# mbed_programmer_2.net
KiCad netlist of a schematic drawn in Altium Designer
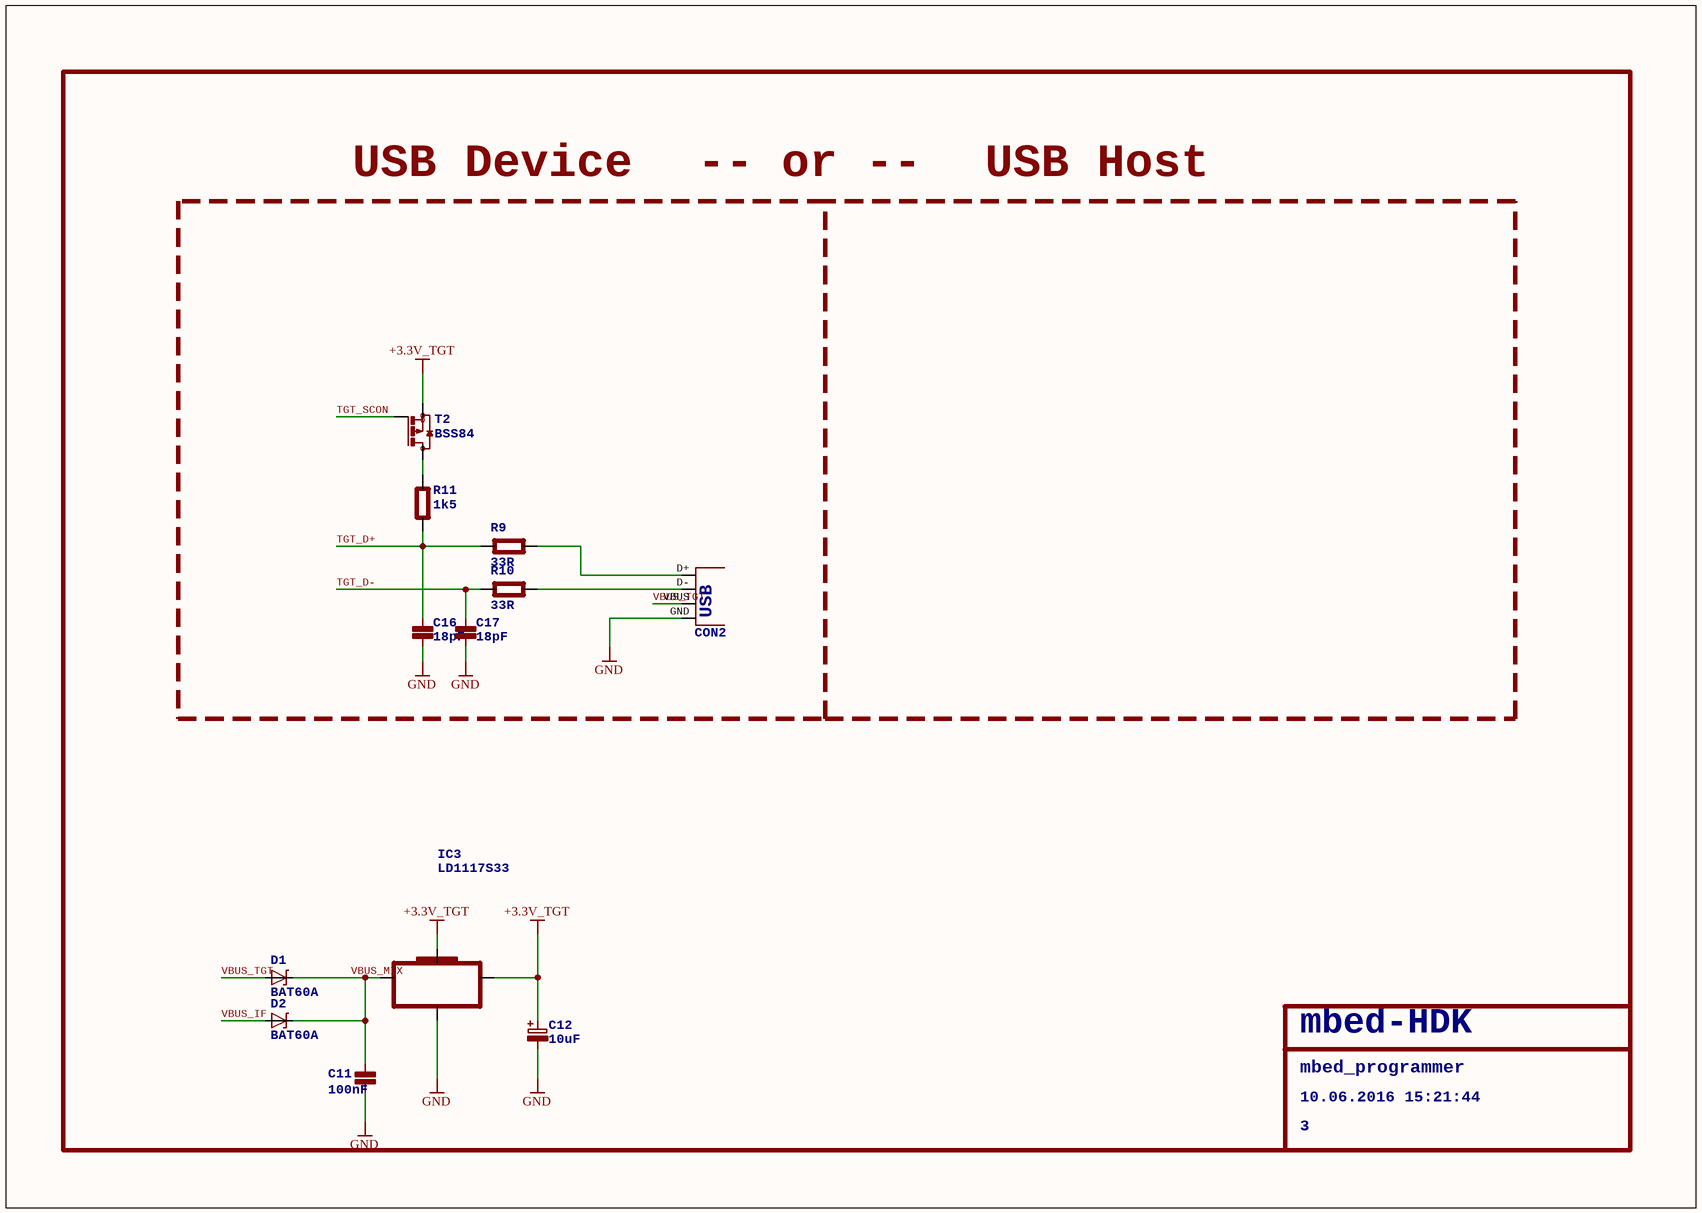
[diagram p0: mbed_programmer_2.SchDoc]

(export (version "E")
  (design (tool "Eeschema 10.0.6"))
  (components
    (comp (ref "C11") (value "100nF") (footprint "0603") (libsource (lib "mbed-HDK") (part "C0603")))
    (comp (ref "C12") (value "10uF") (footprint "CASE-B") (libsource (lib "mbed-HDK") (part "C-POLB")))
    (comp (ref "C16") (value "18pF") (footprint "0603") (libsource (lib "mbed-HDK") (part "C0603")))
    (comp (ref "C17") (value "18pF") (footprint "0603") (libsource (lib "mbed-HDK") (part "C0603")))
    (comp (ref "CON2")
      (value "USB-MB-S")
      (footprint "USB-MB-S")
      (description "USB Connectors")
      (fields (field (name "USB") "USB"))
      (libsource (lib "mbed-HDK") (part "USB-MB-S"))
    )
    (comp (ref "D1") (value "BAT60A") (footprint "BAT60A") (libsource (lib "mbed-HDK") (part "BAT60A")))
    (comp (ref "D2") (value "BAT60A") (footprint "BAT60A") (libsource (lib "mbed-HDK") (part "BAT60A")))
    (comp (ref "IC3")
      (value "LD1117S33")
      (footprint "SOT223")
      (description "VOLTAGE REGULATOR SMD 3,3V")
      (libsource (lib "mbed-HDK") (part "LD1117S33"))
    )
    (comp (ref "R9") (value "33R") (footprint "0603") (libsource (lib "mbed-HDK") (part "R0603")))
    (comp (ref "R10") (value "33R") (footprint "0603") (libsource (lib "mbed-HDK") (part "R0603")))
    (comp (ref "R11") (value "1k5") (footprint "0603") (libsource (lib "mbed-HDK") (part "R0603")))
    (comp (ref "T2")
      (value "BSS84")
      (footprint "SOT23")
      (description "P-CHANNEL MOS FET")
      (libsource (lib "mbed-HDK") (part "BSS84"))
    )
  )
  (nets
    (net (code "1") (name "+3.3V_TGT") (class "Default")
      (node (ref "C12") (pin "1") (pinfunction "1_1") (pintype "passive"))
      (node (ref "IC3") (pin "2") (pinfunction "OUT_2") (pintype "passive"))
      (node (ref "IC3") (pin "4") (pinfunction "K_4") (pintype "passive"))
      (node (ref "T2") (pin "2") (pinfunction "S_2") (pintype "passive"))
    )
    (net (code "2") (name "/TGT_D+") (class "Default")
      (node (ref "C16") (pin "1") (pinfunction "P$1_1") (pintype "passive"))
      (node (ref "R11") (pin "2") (pinfunction "P$2_2") (pintype "passive"))
      (node (ref "R9") (pin "1") (pinfunction "P$1_1") (pintype "passive"))
    )
    (net (code "3") (name "/TGT_D-") (class "Default")
      (node (ref "C17") (pin "1") (pinfunction "P$1_1") (pintype "passive"))
      (node (ref "R10") (pin "1") (pinfunction "P$1_1") (pintype "passive"))
    )
    (net (code "4") (name "/TGT_SCON") (class "Default")
      (node (ref "T2") (pin "1") (pinfunction "G_1") (pintype "passive"))
    )
    (net (code "5") (name "/VBUS_IF") (class "Default")
      (node (ref "D2") (pin "A") (pinfunction "A_A") (pintype "passive"))
    )
    (net (code "6") (name "/VBUS_MIX") (class "Default")
      (node (ref "C11") (pin "1") (pinfunction "P$1_1") (pintype "passive"))
      (node (ref "D1") (pin "K") (pinfunction "K_K") (pintype "passive"))
      (node (ref "D2") (pin "K") (pinfunction "K_K") (pintype "passive"))
      (node (ref "IC3") (pin "3") (pinfunction "IN_3") (pintype "passive"))
    )
    (net (code "7") (name "/VBUS_TGT") (class "Default")
      (node (ref "CON2") (pin "VBUS") (pinfunction "VBUS_VBUS") (pintype "passive"))
      (node (ref "D1") (pin "A") (pinfunction "A_A") (pintype "passive"))
    )
    (net (code "8") (name "GND") (class "Default")
      (node (ref "C11") (pin "2") (pinfunction "P$2_2") (pintype "passive"))
      (node (ref "C12") (pin "2") (pinfunction "2_2") (pintype "passive"))
      (node (ref "C16") (pin "2") (pinfunction "P$2_2") (pintype "passive"))
      (node (ref "C17") (pin "2") (pinfunction "P$2_2") (pintype "passive"))
      (node (ref "CON2") (pin "GND") (pinfunction "GND_GND") (pintype "passive"))
      (node (ref "IC3") (pin "1") (pinfunction "GND_1") (pintype "passive"))
    )
    (net (code "9") (name "Net-(R9-P$2)") (class "Default")
      (node (ref "CON2") (pin "D+") (pinfunction "D+_D+") (pintype "passive"))
      (node (ref "R9") (pin "2") (pinfunction "P$2_2") (pintype "passive"))
    )
    (net (code "10") (name "Net-(R10-P$2)") (class "Default")
      (node (ref "CON2") (pin "D-") (pinfunction "D-_D-") (pintype "passive"))
      (node (ref "R10") (pin "2") (pinfunction "P$2_2") (pintype "passive"))
    )
    (net (code "11") (name "Net-(R11-P$1)") (class "Default")
      (node (ref "R11") (pin "1") (pinfunction "P$1_1") (pintype "passive"))
      (node (ref "T2") (pin "3") (pinfunction "D_3") (pintype "passive"))
    )
  )
)
